# masterboard.net
KiCad netlist of a schematic drawn in EAGLE
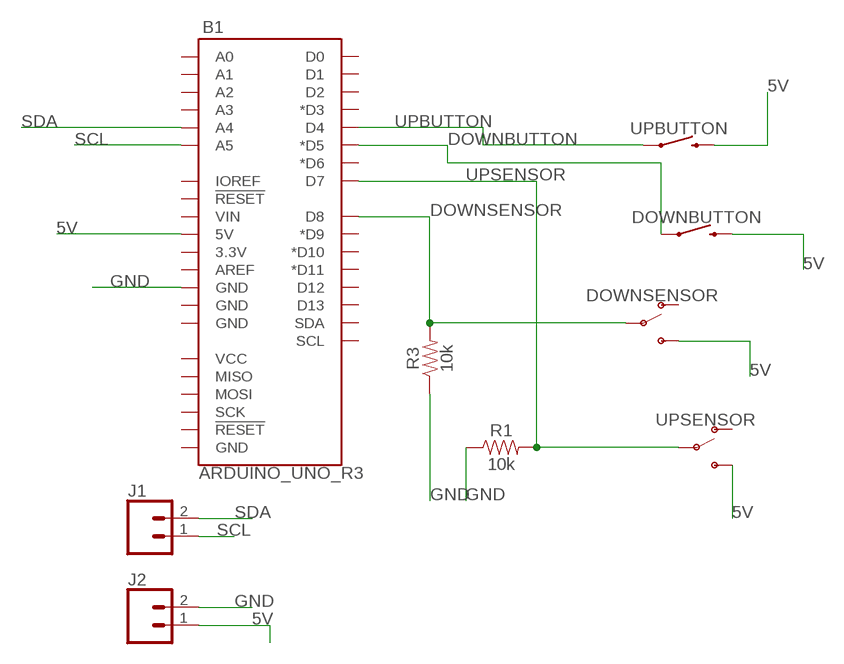
[diagram p0: schematic, sheet 1]

(export (version "E")
  (design (tool "Eeschema 10.0.6"))
  (components
    (comp (ref "B1")
      (value "ARDUINO_UNO_R3")
      (footprint "eagle-import:ARDUINO_R3")
      (libsource (lib "eagle-import") (part "ARDUINO_UNO_R3"))
    )
    (comp (ref "DOWNBUTTON")
      (value "MOMENTARY-SWITCH-SPST-PTH-6.0MM-KIT")
      (footprint "eagle-import:TACTILE_SWITCH_PTH_6.0MM_KIT")
      (libsource (lib "eagle-import") (part "MOMENTARY-SWITCH-SPST-PTH-6.0MM-KIT"))
    )
    (comp (ref "DOWNSENSOR")
      (value "SWITCH-SPDT-PTH-11.6X4.0MM")
      (footprint "eagle-import:SWITCH_SPDT_PTH_11.6X4.0MM")
      (libsource (lib "eagle-import") (part "SWITCH-SPDT-PTH-11.6X4.0MM"))
    )
    (comp (ref "J1")
      (value "CONN_023.5MM")
      (footprint "eagle-import:SCREWTERMINAL-3.5MM-2")
      (libsource (lib "eagle-import") (part "CONN_023.5MM"))
    )
    (comp (ref "J2")
      (value "CONN_023.5MM")
      (footprint "eagle-import:SCREWTERMINAL-3.5MM-2")
      (libsource (lib "eagle-import") (part "CONN_023.5MM"))
    )
    (comp (ref "R1")
      (value "10k")
      (footprint "eagle-import:AXIAL-0.3")
      (libsource (lib "eagle-import") (part "10KOHM-HORIZ-1/4W-1%"))
    )
    (comp (ref "R3")
      (value "10k")
      (footprint "eagle-import:AXIAL-0.3")
      (libsource (lib "eagle-import") (part "10KOHM-HORIZ-1/4W-1%"))
    )
    (comp (ref "UPBUTTON")
      (value "MOMENTARY-SWITCH-SPST-PTH-6.0MM-KIT")
      (footprint "eagle-import:TACTILE_SWITCH_PTH_6.0MM_KIT")
      (libsource (lib "eagle-import") (part "MOMENTARY-SWITCH-SPST-PTH-6.0MM-KIT"))
    )
    (comp (ref "UPSENSOR")
      (value "SWITCH-SPDT-PTH-11.6X4.0MM")
      (footprint "eagle-import:SWITCH_SPDT_PTH_11.6X4.0MM")
      (libsource (lib "eagle-import") (part "SWITCH-SPDT-PTH-11.6X4.0MM"))
    )
  )
  (nets
    (net (code "1") (name "/5V") (class "Default")
      (node (ref "B1") (pin "5V") (pinfunction "5V_5V") (pintype "bidirectional"))
      (node (ref "DOWNBUTTON") (pin "3") (pinfunction "2_3") (pintype "passive"))
      (node (ref "DOWNSENSOR") (pin "3") (pinfunction "S_3") (pintype "passive"))
      (node (ref "J2") (pin "1") (pinfunction "1_1") (pintype "passive"))
      (node (ref "UPBUTTON") (pin "3") (pinfunction "2_3") (pintype "passive"))
      (node (ref "UPSENSOR") (pin "3") (pinfunction "S_3") (pintype "passive"))
    )
    (net (code "2") (name "/DOWNBUTTON") (class "Default")
      (node (ref "B1") (pin "D5") (pinfunction "*D5_D5") (pintype "bidirectional"))
      (node (ref "DOWNBUTTON") (pin "1") (pinfunction "1_1") (pintype "passive"))
    )
    (net (code "3") (name "/DOWNSENSOR") (class "Default")
      (node (ref "B1") (pin "D8") (pinfunction "D8_D8") (pintype "bidirectional"))
      (node (ref "DOWNSENSOR") (pin "2") (pinfunction "P_2") (pintype "passive"))
      (node (ref "R3") (pin "P$2") (pinfunction "2_P$2") (pintype "passive"))
    )
    (net (code "4") (name "/GND") (class "Default")
      (node (ref "B1") (pin "GND@4") (pinfunction "GND_GND@4") (pintype "bidirectional"))
      (node (ref "J2") (pin "2") (pinfunction "2_2") (pintype "passive"))
      (node (ref "R1") (pin "P$1") (pinfunction "1_P$1") (pintype "passive"))
      (node (ref "R3") (pin "P$1") (pinfunction "1_P$1") (pintype "passive"))
    )
    (net (code "5") (name "/SCL") (class "Default")
      (node (ref "B1") (pin "A5") (pinfunction "A5_A5") (pintype "bidirectional"))
      (node (ref "J1") (pin "1") (pinfunction "1_1") (pintype "passive"))
    )
    (net (code "6") (name "/SDA") (class "Default")
      (node (ref "B1") (pin "A4") (pinfunction "A4_A4") (pintype "bidirectional"))
      (node (ref "J1") (pin "2") (pinfunction "2_2") (pintype "passive"))
    )
    (net (code "7") (name "/UPBUTTON") (class "Default")
      (node (ref "B1") (pin "D4") (pinfunction "D4_D4") (pintype "bidirectional"))
      (node (ref "UPBUTTON") (pin "1") (pinfunction "1_1") (pintype "passive"))
    )
    (net (code "8") (name "/UPSENSOR") (class "Default")
      (node (ref "B1") (pin "D7") (pinfunction "D7_D7") (pintype "bidirectional"))
      (node (ref "R1") (pin "P$2") (pinfunction "2_P$2") (pintype "passive"))
      (node (ref "UPSENSOR") (pin "2") (pinfunction "P_2") (pintype "passive"))
    )
    (net (code "9") (name "unconnected-(B1-*D3-PadD3)") (class "Default")
      (node (ref "B1") (pin "D3") (pinfunction "*D3_D3") (pintype "bidirectional"))
    )
    (net (code "10") (name "unconnected-(B1-*D6-PadD6)") (class "Default")
      (node (ref "B1") (pin "D6") (pinfunction "*D6_D6") (pintype "bidirectional"))
    )
    (net (code "11") (name "unconnected-(B1-*D9-PadD9)") (class "Default")
      (node (ref "B1") (pin "D9") (pinfunction "*D9_D9") (pintype "bidirectional"))
    )
    (net (code "12") (name "unconnected-(B1-*D10-PadD10)") (class "Default")
      (node (ref "B1") (pin "D10") (pinfunction "*D10_D10") (pintype "bidirectional"))
    )
    (net (code "13") (name "unconnected-(B1-*D11-PadD11)") (class "Default")
      (node (ref "B1") (pin "D11") (pinfunction "*D11_D11") (pintype "bidirectional"))
    )
    (net (code "14") (name "unconnected-(B1-GND-PadGND@1)") (class "Default")
      (node (ref "B1") (pin "GND@1") (pinfunction "GND_GND@1") (pintype "bidirectional"))
    )
    (net (code "15") (name "unconnected-(B1-GND-PadGND@2)") (class "Default")
      (node (ref "B1") (pin "GND@2") (pinfunction "GND_GND@2") (pintype "bidirectional"))
    )
    (net (code "16") (name "unconnected-(B1-GND-PadGND@3)") (class "Default")
      (node (ref "B1") (pin "GND@3") (pinfunction "GND_GND@3") (pintype "bidirectional"))
    )
    (net (code "17") (name "unconnected-(B1-Pad3.3V)") (class "Default")
      (node (ref "B1") (pin "3.3V") (pinfunction "3.3V_3.3V") (pintype "bidirectional"))
    )
    (net (code "18") (name "unconnected-(B1-PadA0)") (class "Default")
      (node (ref "B1") (pin "A0") (pinfunction "A0_A0") (pintype "bidirectional"))
    )
    (net (code "19") (name "unconnected-(B1-PadA1)") (class "Default")
      (node (ref "B1") (pin "A1") (pinfunction "A1_A1") (pintype "bidirectional"))
    )
    (net (code "20") (name "unconnected-(B1-PadA2)") (class "Default")
      (node (ref "B1") (pin "A2") (pinfunction "A2_A2") (pintype "bidirectional"))
    )
    (net (code "21") (name "unconnected-(B1-PadA3)") (class "Default")
      (node (ref "B1") (pin "A3") (pinfunction "A3_A3") (pintype "bidirectional"))
    )
    (net (code "22") (name "unconnected-(B1-PadAREF)") (class "Default")
      (node (ref "B1") (pin "AREF") (pinfunction "AREF_AREF") (pintype "bidirectional"))
    )
    (net (code "23") (name "unconnected-(B1-PadD0)") (class "Default")
      (node (ref "B1") (pin "D0") (pinfunction "D0_D0") (pintype "bidirectional"))
    )
    (net (code "24") (name "unconnected-(B1-PadD1)") (class "Default")
      (node (ref "B1") (pin "D1") (pinfunction "D1_D1") (pintype "bidirectional"))
    )
    (net (code "25") (name "unconnected-(B1-PadD2)") (class "Default")
      (node (ref "B1") (pin "D2") (pinfunction "D2_D2") (pintype "bidirectional"))
    )
    (net (code "26") (name "unconnected-(B1-PadD12)") (class "Default")
      (node (ref "B1") (pin "D12") (pinfunction "D12_D12") (pintype "bidirectional"))
    )
    (net (code "27") (name "unconnected-(B1-PadD13)") (class "Default")
      (node (ref "B1") (pin "D13") (pinfunction "D13_D13") (pintype "bidirectional"))
    )
    (net (code "28") (name "unconnected-(B1-PadIOREF)") (class "Default")
      (node (ref "B1") (pin "IOREF") (pinfunction "IOREF_IOREF") (pintype "bidirectional"))
    )
    (net (code "29") (name "unconnected-(B1-PadMISO)") (class "Default")
      (node (ref "B1") (pin "MISO") (pinfunction "MISO_MISO") (pintype "bidirectional"))
    )
    (net (code "30") (name "unconnected-(B1-PadMOSI)") (class "Default")
      (node (ref "B1") (pin "MOSI") (pinfunction "MOSI_MOSI") (pintype "bidirectional"))
    )
    (net (code "31") (name "unconnected-(B1-PadSCK)") (class "Default")
      (node (ref "B1") (pin "SCK") (pinfunction "SCK_SCK") (pintype "bidirectional"))
    )
    (net (code "32") (name "unconnected-(B1-PadSCL)") (class "Default")
      (node (ref "B1") (pin "SCL") (pinfunction "SCL_SCL") (pintype "bidirectional"))
    )
    (net (code "33") (name "unconnected-(B1-PadSDA)") (class "Default")
      (node (ref "B1") (pin "SDA") (pinfunction "SDA_SDA") (pintype "bidirectional"))
    )
    (net (code "34") (name "unconnected-(B1-PadVCC)") (class "Default")
      (node (ref "B1") (pin "VCC") (pinfunction "VCC_VCC") (pintype "bidirectional"))
    )
    (net (code "35") (name "unconnected-(B1-PadVIN)") (class "Default")
      (node (ref "B1") (pin "VIN") (pinfunction "VIN_VIN") (pintype "bidirectional"))
    )
    (net (code "36") (name "unconnected-(B1-~{RESET}-PadRESET@1)") (class "Default")
      (node (ref "B1") (pin "RESET@1") (pinfunction "~{RESET}_RESET@1") (pintype "bidirectional"))
    )
    (net (code "37") (name "unconnected-(B1-~{RESET}-PadRESET@2)") (class "Default")
      (node (ref "B1") (pin "RESET@2") (pinfunction "~{RESET}_RESET@2") (pintype "bidirectional"))
    )
    (net (code "38") (name "unconnected-(DOWNSENSOR-O-Pad1)") (class "Default")
      (node (ref "DOWNSENSOR") (pin "1") (pinfunction "O_1") (pintype "passive"))
    )
    (net (code "39") (name "unconnected-(UPSENSOR-O-Pad1)") (class "Default")
      (node (ref "UPSENSOR") (pin "1") (pinfunction "O_1") (pintype "passive"))
    )
  )
)
